# USB.net
KiCad netlist of a schematic drawn in Altium Designer
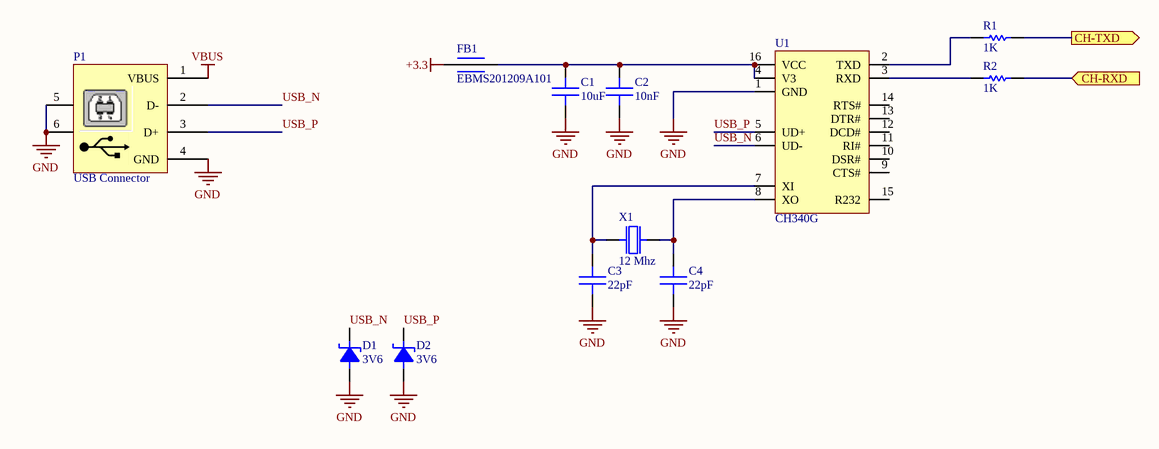
[diagram p0: USB.SchDoc]

(export (version "E")
  (design (tool "Eeschema 10.0.6"))
  (components
    (comp (ref "C1")
      (value "10uF")
      (footprint "C-0805")
      (description "SMD 0805")
      (libsource (lib "IOElectro") (part "CAP"))
    )
    (comp (ref "C2")
      (value "10nF")
      (footprint "C-0805")
      (description "SMD 0805")
      (libsource (lib "IOElectro") (part "CAP"))
    )
    (comp (ref "C3")
      (value "22pF")
      (footprint "C-0805")
      (description "SMD 0805")
      (libsource (lib "IOElectro") (part "CAP"))
    )
    (comp (ref "C4")
      (value "22pF")
      (footprint "C-0805")
      (description "SMD 0805")
      (libsource (lib "IOElectro") (part "CAP"))
    )
    (comp (ref "D1")
      (value "3V6")
      (footprint "SOD80")
      (description "SMD MiniMELF")
      (libsource (lib "IOElectro") (part "DIODE-Z"))
    )
    (comp (ref "D2")
      (value "3V6")
      (footprint "SOD80")
      (description "SMD MiniMELF")
      (libsource (lib "IOElectro") (part "DIODE-Z"))
    )
    (comp (ref "FB1")
      (value "EBMS201209A101")
      (footprint "L-0805")
      (description "FERRITE BEAD 0805 100R 100Mhz")
      (libsource (lib "Schlib") (part "EBMS201209A101"))
    )
    (comp (ref "P1")
      (value "USB Connector")
      (footprint "USB2.5-2H4E")
      (description "USB Connector-B Type")
      (fields (field (name "DESIGNER") "Eng. Saeid Jorablo"))
      (libsource (lib "IOElectro") (part "USB-B"))
    )
    (comp (ref "R1")
      (value "1K")
      (footprint "R-0805")
      (description "0805")
      (libsource (lib "IOElectro") (part "RES"))
    )
    (comp (ref "R2")
      (value "1K")
      (footprint "R-0805")
      (description "0805")
      (libsource (lib "IOElectro") (part "RES"))
    )
    (comp (ref "U1")
      (value "CH340G")
      (footprint "SOP-16")
      (description "IC USB to Serial")
      (libsource (lib "IOElectro") (part "CH340G"))
    )
    (comp (ref "X1")
      (value "12 Mhz")
      (footprint "XTAL-DIP_Small")
      (description "Crystal oscillator")
      (libsource (lib "IOElectro") (part "XTAL"))
    )
  )
  (nets
    (net (code "1") (name "+3.3") (class "Default")
      (node (ref "FB1") (pin "1") (pinfunction "1_1") (pintype "passive"))
    )
    (net (code "2") (name "/CH-RXD") (class "Default")
      (node (ref "R2") (pin "2") (pinfunction "2_2") (pintype "passive"))
    )
    (net (code "3") (name "/CH-TXD") (class "Default")
      (node (ref "R1") (pin "2") (pinfunction "2_2") (pintype "passive"))
    )
    (net (code "4") (name "/USB_N") (class "Default")
      (node (ref "D1") (pin "K") (pinfunction "K_K") (pintype "passive"))
      (node (ref "P1") (pin "2") (pinfunction "D-_2") (pintype "passive"))
      (node (ref "U1") (pin "6") (pinfunction "UD-_6") (pintype "passive"))
    )
    (net (code "5") (name "/USB_P") (class "Default")
      (node (ref "D2") (pin "K") (pinfunction "K_K") (pintype "passive"))
      (node (ref "P1") (pin "3") (pinfunction "D+_3") (pintype "passive"))
      (node (ref "U1") (pin "5") (pinfunction "UD+_5") (pintype "passive"))
    )
    (net (code "6") (name "GND") (class "Default")
      (node (ref "C1") (pin "2") (pinfunction "2_2") (pintype "passive"))
      (node (ref "C2") (pin "2") (pinfunction "2_2") (pintype "passive"))
      (node (ref "C3") (pin "2") (pinfunction "2_2") (pintype "passive"))
      (node (ref "C4") (pin "2") (pinfunction "2_2") (pintype "passive"))
      (node (ref "D1") (pin "A") (pinfunction "A_A") (pintype "passive"))
      (node (ref "D2") (pin "A") (pinfunction "A_A") (pintype "passive"))
      (node (ref "P1") (pin "4") (pinfunction "GND_4") (pintype "power_in"))
      (node (ref "P1") (pin "5") (pinfunction "5_5") (pintype "passive"))
      (node (ref "P1") (pin "6") (pinfunction "6_6") (pintype "passive"))
      (node (ref "U1") (pin "1") (pinfunction "GND_1") (pintype "passive"))
    )
    (net (code "7") (name "Net-(U1-RXD)") (class "Default")
      (node (ref "R2") (pin "1") (pinfunction "1_1") (pintype "passive"))
      (node (ref "U1") (pin "3") (pinfunction "RXD_3") (pintype "passive"))
    )
    (net (code "8") (name "Net-(U1-TXD)") (class "Default")
      (node (ref "R1") (pin "1") (pinfunction "1_1") (pintype "passive"))
      (node (ref "U1") (pin "2") (pinfunction "TXD_2") (pintype "passive"))
    )
    (net (code "9") (name "Net-(U1-V3)") (class "Default")
      (node (ref "C1") (pin "1") (pinfunction "1_1") (pintype "passive"))
      (node (ref "C2") (pin "1") (pinfunction "1_1") (pintype "passive"))
      (node (ref "FB1") (pin "2") (pinfunction "2_2") (pintype "passive"))
      (node (ref "U1") (pin "16") (pinfunction "VCC_16") (pintype "passive"))
      (node (ref "U1") (pin "4") (pinfunction "V3_4") (pintype "passive"))
    )
    (net (code "10") (name "Net-(U1-XI)") (class "Default")
      (node (ref "C3") (pin "1") (pinfunction "1_1") (pintype "passive"))
      (node (ref "U1") (pin "7") (pinfunction "XI_7") (pintype "passive"))
      (node (ref "X1") (pin "2") (pinfunction "2_2") (pintype "passive"))
    )
    (net (code "11") (name "Net-(U1-XO)") (class "Default")
      (node (ref "C4") (pin "1") (pinfunction "1_1") (pintype "passive"))
      (node (ref "U1") (pin "8") (pinfunction "XO_8") (pintype "passive"))
      (node (ref "X1") (pin "1") (pinfunction "1_1") (pintype "passive"))
    )
    (net (code "12") (name "VBUS") (class "Default")
      (node (ref "P1") (pin "1") (pinfunction "VBUS_1") (pintype "power_in"))
    )
    (net (code "13") (name "unconnected-(U1-CTS#-Pad9)") (class "Default")
      (node (ref "U1") (pin "9") (pinfunction "CTS#_9") (pintype "passive"))
    )
    (net (code "14") (name "unconnected-(U1-DCD#-Pad12)") (class "Default")
      (node (ref "U1") (pin "12") (pinfunction "DCD#_12") (pintype "passive"))
    )
    (net (code "15") (name "unconnected-(U1-DSR#-Pad10)") (class "Default")
      (node (ref "U1") (pin "10") (pinfunction "DSR#_10") (pintype "passive"))
    )
    (net (code "16") (name "unconnected-(U1-DTR#-Pad13)") (class "Default")
      (node (ref "U1") (pin "13") (pinfunction "DTR#_13") (pintype "passive"))
    )
    (net (code "17") (name "unconnected-(U1-R232-Pad15)") (class "Default")
      (node (ref "U1") (pin "15") (pinfunction "R232_15") (pintype "passive"))
    )
    (net (code "18") (name "unconnected-(U1-RI#-Pad11)") (class "Default")
      (node (ref "U1") (pin "11") (pinfunction "RI#_11") (pintype "passive"))
    )
    (net (code "19") (name "unconnected-(U1-RTS#-Pad14)") (class "Default")
      (node (ref "U1") (pin "14") (pinfunction "RTS#_14") (pintype "passive"))
    )
  )
)
